# Power_Dev_revA_2.net
KiCad netlist of a schematic drawn in EAGLE
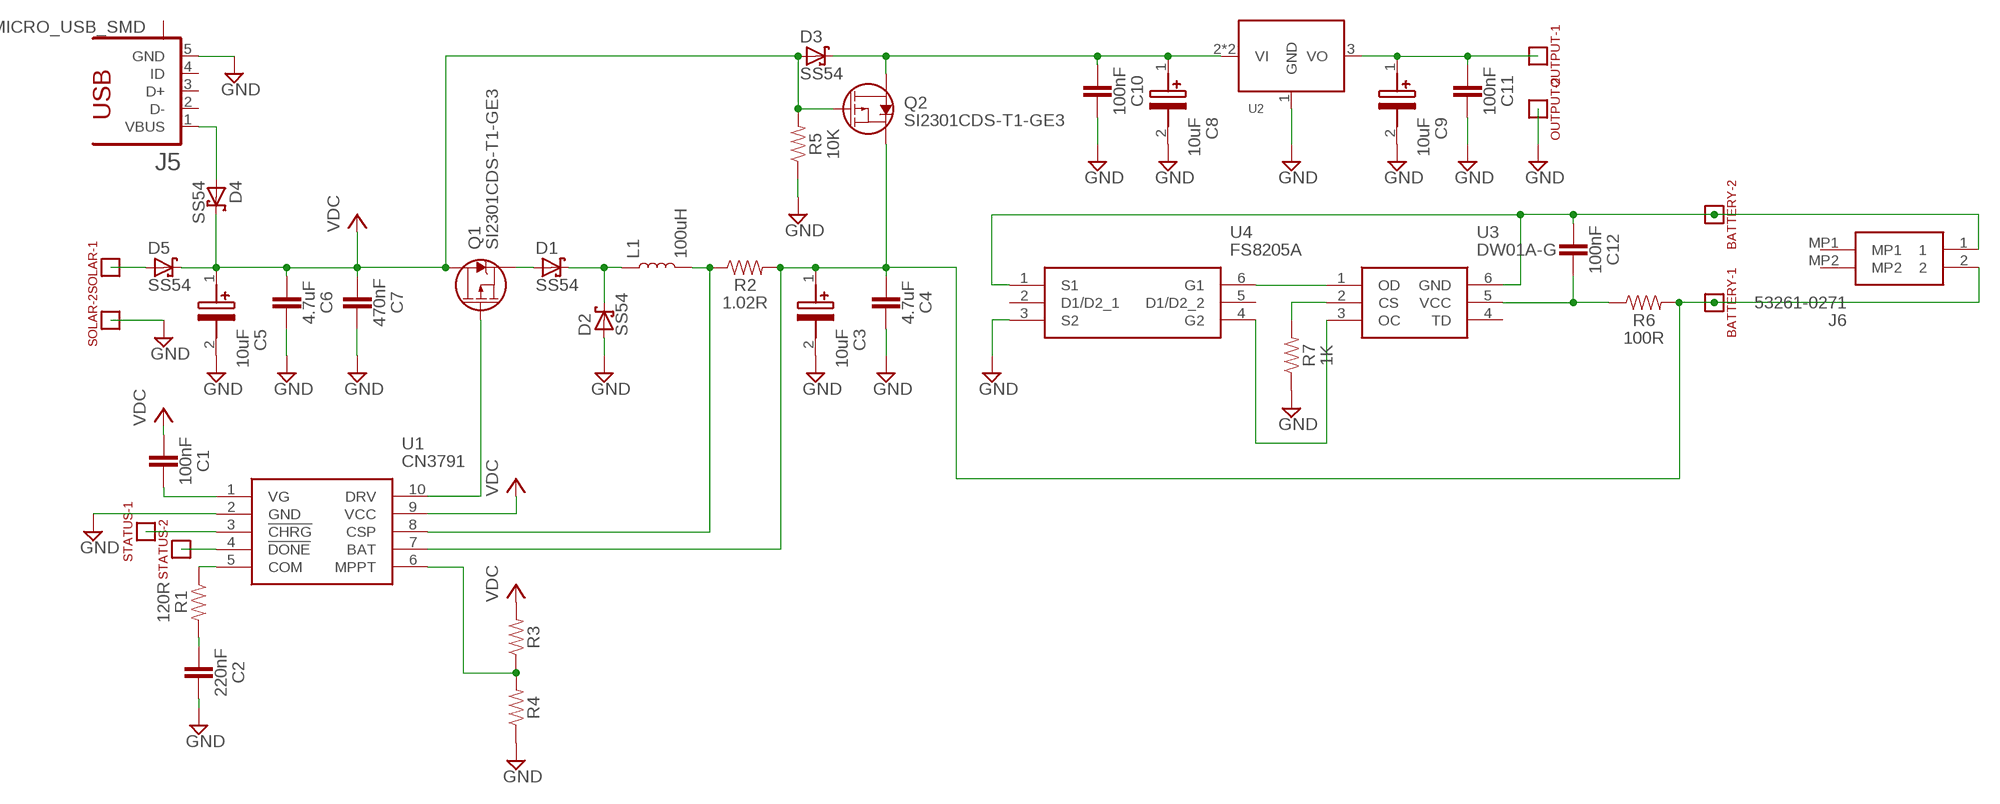
[diagram p0: schematic, sheet 1]

(export (version "E")
  (design (tool "Eeschema 10.0.6"))
  (components
    (comp (ref "BATTERY")
      (value "HEADER_2PIN")
      (footprint "eagle-import:HEADER_2PIN")
      (libsource (lib "eagle-import") (part "HEADER_2PIN"))
    )
    (comp (ref "C1")
      (value "100nF")
      (footprint "eagle-import:0402")
      (libsource (lib "eagle-import") (part "C_0402"))
    )
    (comp (ref "C2")
      (value "220nF")
      (footprint "eagle-import:0603")
      (libsource (lib "eagle-import") (part "C_0603"))
    )
    (comp (ref "C3")
      (value "10uF")
      (footprint "eagle-import:6MM_SMD_ECAP")
      (libsource (lib "eagle-import") (part "6.3MM_SMD_ECAP"))
    )
    (comp (ref "C4")
      (value "4.7uF")
      (footprint "eagle-import:1206")
      (libsource (lib "eagle-import") (part "C_1206"))
    )
    (comp (ref "C5")
      (value "10uF")
      (footprint "eagle-import:6MM_SMD_ECAP")
      (libsource (lib "eagle-import") (part "6.3MM_SMD_ECAP"))
    )
    (comp (ref "C6")
      (value "4.7uF")
      (footprint "eagle-import:1206")
      (libsource (lib "eagle-import") (part "C_1206"))
    )
    (comp (ref "C7")
      (value "470nF")
      (footprint "eagle-import:0805")
      (libsource (lib "eagle-import") (part "C_0805"))
    )
    (comp (ref "C8")
      (value "10uF")
      (footprint "eagle-import:6MM_SMD_ECAP")
      (libsource (lib "eagle-import") (part "6.3MM_SMD_ECAP"))
    )
    (comp (ref "C9")
      (value "10uF")
      (footprint "eagle-import:6MM_SMD_ECAP")
      (libsource (lib "eagle-import") (part "6.3MM_SMD_ECAP"))
    )
    (comp (ref "C10")
      (value "100nF")
      (footprint "eagle-import:0402")
      (libsource (lib "eagle-import") (part "C_0402"))
    )
    (comp (ref "C11")
      (value "100nF")
      (footprint "eagle-import:0402")
      (libsource (lib "eagle-import") (part "C_0402"))
    )
    (comp (ref "C12")
      (value "100nF")
      (footprint "eagle-import:0402")
      (libsource (lib "eagle-import") (part "C_0402"))
    )
    (comp (ref "D1")
      (value "SS54")
      (footprint "eagle-import:SMA(DO-214AC)")
      (libsource (lib "eagle-import") (part "DIODE_SCHOTTKY_SMA"))
    )
    (comp (ref "D2")
      (value "SS54")
      (footprint "eagle-import:SMA(DO-214AC)")
      (libsource (lib "eagle-import") (part "DIODE_SCHOTTKY_SMA"))
    )
    (comp (ref "D3")
      (value "SS54")
      (footprint "eagle-import:SMA(DO-214AC)")
      (libsource (lib "eagle-import") (part "DIODE_SCHOTTKY_SMA"))
    )
    (comp (ref "D4")
      (value "SS54")
      (footprint "eagle-import:SMA(DO-214AC)")
      (libsource (lib "eagle-import") (part "DIODE_SCHOTTKY_SMA"))
    )
    (comp (ref "D5")
      (value "SS54")
      (footprint "eagle-import:SMA(DO-214AC)")
      (libsource (lib "eagle-import") (part "DIODE_SCHOTTKY_SMA"))
    )
    (comp (ref "J5")
      (value "MICRO_USB_SMD")
      (footprint "eagle-import:10118192-0002LF")
      (libsource (lib "eagle-import") (part "MICRO_USB_SMD"))
    )
    (comp (ref "J6")
      (value "53261-0271")
      (footprint "eagle-import:532610271")
      (fields (field (name "MOUSER_PART_NUMBER") "538-53261-0271"))
      (libsource (lib "eagle-import") (part "53261-0271"))
    )
    (comp (ref "L1")
      (value "100uH")
      (footprint "eagle-import:L_SMD,7X7.8MM")
      (libsource (lib "eagle-import") (part "L_SMD,7X7.8MM"))
    )
    (comp (ref "OUTPUT")
      (value "HEADER_2PIN")
      (footprint "eagle-import:HEADER_2PIN")
      (libsource (lib "eagle-import") (part "HEADER_2PIN"))
    )
    (comp (ref "Q1")
      (value "SI2301CDS-T1-GE3")
      (footprint "eagle-import:SOT-23")
      (libsource (lib "eagle-import") (part "MOSFET_P_SOT23"))
    )
    (comp (ref "Q2")
      (value "SI2301CDS-T1-GE3")
      (footprint "eagle-import:SOT-23")
      (libsource (lib "eagle-import") (part "MOSFET_P_SOT23"))
    )
    (comp (ref "R1")
      (value "120R")
      (footprint "eagle-import:0805")
      (libsource (lib "eagle-import") (part "R_0805"))
    )
    (comp (ref "R2")
      (value "1.02R")
      (footprint "eagle-import:1206")
      (libsource (lib "eagle-import") (part "R_1206"))
    )
    (comp (ref "R3")
      (value "RESISTOR_TH")
      (footprint "eagle-import:RESISTOR_TH")
      (libsource (lib "eagle-import") (part "RESISTOR_TH"))
    )
    (comp (ref "R4")
      (value "RESISTOR_TH")
      (footprint "eagle-import:RESISTOR_TH")
      (libsource (lib "eagle-import") (part "RESISTOR_TH"))
    )
    (comp (ref "R5")
      (value "10K")
      (footprint "eagle-import:0402")
      (libsource (lib "eagle-import") (part "R_0402"))
    )
    (comp (ref "R6")
      (value "100R")
      (footprint "eagle-import:0402")
      (libsource (lib "eagle-import") (part "R_0402"))
    )
    (comp (ref "R7")
      (value "1K")
      (footprint "eagle-import:0402")
      (libsource (lib "eagle-import") (part "R_0402"))
    )
    (comp (ref "SOLAR")
      (value "HEADER_2PIN")
      (footprint "eagle-import:HEADER_2PIN")
      (libsource (lib "eagle-import") (part "HEADER_2PIN"))
    )
    (comp (ref "STATUS")
      (value "HEADER_2PIN")
      (footprint "eagle-import:HEADER_2PIN")
      (libsource (lib "eagle-import") (part "HEADER_2PIN"))
    )
    (comp (ref "U1")
      (value "CN3791")
      (footprint "eagle-import:SOP100P600X175-10N")
      (libsource (lib "eagle-import") (part "CN3791"))
    )
    (comp (ref "U2")
      (value "LDO_SOT89")
      (footprint "eagle-import:SOT-89-3")
      (libsource (lib "eagle-import") (part "LDO_SOT89"))
    )
    (comp (ref "U3")
      (value "DW01A-G")
      (footprint "eagle-import:SOT95P280X135-6N")
      (libsource (lib "eagle-import") (part "DW01A-G"))
    )
    (comp (ref "U4")
      (value "FS8205A")
      (footprint "eagle-import:SOT95P280X125-6N")
      (libsource (lib "eagle-import") (part "FS8205A"))
    )
  )
  (nets
    (net (code "1") (name "GND") (class "Default")
      (node (ref "C10") (pin "2") (pinfunction "2_2") (pintype "passive"))
      (node (ref "C11") (pin "2") (pinfunction "2_2") (pintype "passive"))
      (node (ref "C2") (pin "2") (pinfunction "2_2") (pintype "passive"))
      (node (ref "C3") (pin "2") (pinfunction "-_2") (pintype "bidirectional"))
      (node (ref "C4") (pin "2") (pinfunction "2_2") (pintype "passive"))
      (node (ref "C5") (pin "2") (pinfunction "-_2") (pintype "bidirectional"))
      (node (ref "C6") (pin "2") (pinfunction "2_2") (pintype "passive"))
      (node (ref "C7") (pin "2") (pinfunction "2_2") (pintype "passive"))
      (node (ref "C8") (pin "2") (pinfunction "-_2") (pintype "bidirectional"))
      (node (ref "C9") (pin "2") (pinfunction "-_2") (pintype "bidirectional"))
      (node (ref "D2") (pin "2") (pinfunction "A_2") (pintype "passive"))
      (node (ref "J5") (pin "5") (pinfunction "GND_5") (pintype "passive"))
      (node (ref "OUTPUT") (pin "P$2") (pinfunction "P$1_P$2") (pintype "bidirectional"))
      (node (ref "R4") (pin "P$1") (pinfunction "1_P$1") (pintype "passive"))
      (node (ref "R5") (pin "1") (pinfunction "1_1") (pintype "passive"))
      (node (ref "R7") (pin "1") (pinfunction "1_1") (pintype "passive"))
      (node (ref "SOLAR") (pin "P$2") (pinfunction "P$1_P$2") (pintype "bidirectional"))
      (node (ref "U1") (pin "2") (pinfunction "GND_2") (pintype "bidirectional"))
      (node (ref "U2") (pin "1") (pinfunction "GND_1") (pintype "bidirectional"))
      (node (ref "U4") (pin "3") (pinfunction "S2_3") (pintype "bidirectional"))
    )
    (net (code "2") (name "Net-(BATTERYB-P$1)") (class "Default")
      (node (ref "BATTERY") (pin "P$2") (pinfunction "P$1_P$2") (pintype "bidirectional"))
      (node (ref "C12") (pin "1") (pinfunction "1_1") (pintype "passive"))
      (node (ref "J6") (pin "1") (pinfunction "1_1") (pintype "bidirectional"))
      (node (ref "U3") (pin "6") (pinfunction "GND_6") (pintype "bidirectional"))
      (node (ref "U4") (pin "1") (pinfunction "S1_1") (pintype "bidirectional"))
    )
    (net (code "3") (name "Net-(C2-Pad1)") (class "Default")
      (node (ref "C2") (pin "1") (pinfunction "1_1") (pintype "passive"))
      (node (ref "R1") (pin "2") (pinfunction "2_2") (pintype "passive"))
    )
    (net (code "4") (name "Net-(C3-+)") (class "Default")
      (node (ref "BATTERY") (pin "P$1") (pinfunction "P$1_P$1") (pintype "bidirectional"))
      (node (ref "C3") (pin "1") (pinfunction "+_1") (pintype "bidirectional"))
      (node (ref "C4") (pin "1") (pinfunction "1_1") (pintype "passive"))
      (node (ref "J6") (pin "2") (pinfunction "2_2") (pintype "bidirectional"))
      (node (ref "Q2") (pin "3") (pinfunction "S_3") (pintype "bidirectional"))
      (node (ref "R2") (pin "2") (pinfunction "2_2") (pintype "passive"))
      (node (ref "R6") (pin "2") (pinfunction "2_2") (pintype "passive"))
      (node (ref "U1") (pin "7") (pinfunction "BAT_7") (pintype "bidirectional"))
    )
    (net (code "5") (name "Net-(C8-+)") (class "Default")
      (node (ref "C10") (pin "1") (pinfunction "1_1") (pintype "passive"))
      (node (ref "C8") (pin "1") (pinfunction "+_1") (pintype "bidirectional"))
      (node (ref "D3") (pin "1") (pinfunction "C_1") (pintype "passive"))
      (node (ref "Q2") (pin "2") (pinfunction "D_2") (pintype "bidirectional"))
      (node (ref "U2") (pin "2") (pinfunction "VI_2") (pintype "bidirectional"))
      (node (ref "U2") (pin "4") (pinfunction "VI_4") (pintype "bidirectional"))
    )
    (net (code "6") (name "Net-(C9-+)") (class "Default")
      (node (ref "C11") (pin "1") (pinfunction "1_1") (pintype "passive"))
      (node (ref "C9") (pin "1") (pinfunction "+_1") (pintype "bidirectional"))
      (node (ref "OUTPUT") (pin "P$1") (pinfunction "P$1_P$1") (pintype "bidirectional"))
      (node (ref "U2") (pin "3") (pinfunction "VO_3") (pintype "bidirectional"))
    )
    (net (code "7") (name "Net-(D1-A)") (class "Default")
      (node (ref "D1") (pin "2") (pinfunction "A_2") (pintype "passive"))
      (node (ref "Q1") (pin "3") (pinfunction "S_3") (pintype "bidirectional"))
    )
    (net (code "8") (name "Net-(D1-C)") (class "Default")
      (node (ref "D1") (pin "1") (pinfunction "C_1") (pintype "passive"))
      (node (ref "D2") (pin "1") (pinfunction "C_1") (pintype "passive"))
      (node (ref "L1") (pin "P$1") (pinfunction "1_P$1") (pintype "passive"))
    )
    (net (code "9") (name "Net-(D4-A)") (class "Default")
      (node (ref "D4") (pin "2") (pinfunction "A_2") (pintype "passive"))
      (node (ref "J5") (pin "1") (pinfunction "VBUS_1") (pintype "passive"))
    )
    (net (code "10") (name "Net-(D5-A)") (class "Default")
      (node (ref "D5") (pin "2") (pinfunction "A_2") (pintype "passive"))
      (node (ref "SOLAR") (pin "P$1") (pinfunction "P$1_P$1") (pintype "bidirectional"))
    )
    (net (code "11") (name "Net-(L1-2)") (class "Default")
      (node (ref "L1") (pin "P$2") (pinfunction "2_P$2") (pintype "passive"))
      (node (ref "R2") (pin "1") (pinfunction "1_1") (pintype "passive"))
      (node (ref "U1") (pin "8") (pinfunction "CSP_8") (pintype "bidirectional"))
    )
    (net (code "12") (name "Net-(Q1-G)") (class "Default")
      (node (ref "Q1") (pin "1") (pinfunction "G_1") (pintype "bidirectional"))
      (node (ref "U1") (pin "10") (pinfunction "DRV_10") (pintype "bidirectional"))
    )
    (net (code "13") (name "Net-(R3-1)") (class "Default")
      (node (ref "R3") (pin "P$1") (pinfunction "1_P$1") (pintype "passive"))
      (node (ref "R4") (pin "P$2") (pinfunction "2_P$2") (pintype "passive"))
      (node (ref "U1") (pin "6") (pinfunction "MPPT_6") (pintype "bidirectional"))
    )
    (net (code "14") (name "Net-(STATUSB-P$1)") (class "Default")
      (node (ref "STATUS") (pin "P$2") (pinfunction "P$1_P$2") (pintype "bidirectional"))
      (node (ref "U1") (pin "4") (pinfunction "~{DONE}_4") (pintype "bidirectional"))
    )
    (net (code "15") (name "Net-(U1-COM)") (class "Default")
      (node (ref "R1") (pin "1") (pinfunction "1_1") (pintype "passive"))
      (node (ref "U1") (pin "5") (pinfunction "COM_5") (pintype "bidirectional"))
    )
    (net (code "16") (name "Net-(U1-VG)") (class "Default")
      (node (ref "C1") (pin "2") (pinfunction "2_2") (pintype "passive"))
      (node (ref "U1") (pin "1") (pinfunction "VG_1") (pintype "bidirectional"))
    )
    (net (code "17") (name "Net-(U1-~{CHRG})") (class "Default")
      (node (ref "STATUS") (pin "P$1") (pinfunction "P$1_P$1") (pintype "bidirectional"))
      (node (ref "U1") (pin "3") (pinfunction "~{CHRG}_3") (pintype "bidirectional"))
    )
    (net (code "18") (name "Net-(U3-CS)") (class "Default")
      (node (ref "R7") (pin "2") (pinfunction "2_2") (pintype "passive"))
      (node (ref "U3") (pin "2") (pinfunction "CS_2") (pintype "bidirectional"))
    )
    (net (code "19") (name "Net-(U3-OC)") (class "Default")
      (node (ref "U3") (pin "3") (pinfunction "OC_3") (pintype "bidirectional"))
      (node (ref "U4") (pin "4") (pinfunction "G2_4") (pintype "bidirectional"))
    )
    (net (code "20") (name "Net-(U3-OD)") (class "Default")
      (node (ref "U3") (pin "1") (pinfunction "OD_1") (pintype "bidirectional"))
      (node (ref "U4") (pin "6") (pinfunction "G1_6") (pintype "bidirectional"))
    )
    (net (code "21") (name "Net-(U3-VCC)") (class "Default")
      (node (ref "C12") (pin "2") (pinfunction "2_2") (pintype "passive"))
      (node (ref "R6") (pin "1") (pinfunction "1_1") (pintype "passive"))
      (node (ref "U3") (pin "5") (pinfunction "VCC_5") (pintype "bidirectional"))
    )
    (net (code "22") (name "VDC") (class "Default")
      (node (ref "C1") (pin "1") (pinfunction "1_1") (pintype "passive"))
      (node (ref "C5") (pin "1") (pinfunction "+_1") (pintype "bidirectional"))
      (node (ref "C6") (pin "1") (pinfunction "1_1") (pintype "passive"))
      (node (ref "C7") (pin "1") (pinfunction "1_1") (pintype "passive"))
      (node (ref "D3") (pin "2") (pinfunction "A_2") (pintype "passive"))
      (node (ref "D4") (pin "1") (pinfunction "C_1") (pintype "passive"))
      (node (ref "D5") (pin "1") (pinfunction "C_1") (pintype "passive"))
      (node (ref "Q1") (pin "2") (pinfunction "D_2") (pintype "bidirectional"))
      (node (ref "Q2") (pin "1") (pinfunction "G_1") (pintype "bidirectional"))
      (node (ref "R3") (pin "P$2") (pinfunction "2_P$2") (pintype "passive"))
      (node (ref "R5") (pin "2") (pinfunction "2_2") (pintype "passive"))
      (node (ref "U1") (pin "9") (pinfunction "VCC_9") (pintype "bidirectional"))
    )
    (net (code "23") (name "unconnected-(J5-D+-Pad3)") (class "Default")
      (node (ref "J5") (pin "3") (pinfunction "D+_3") (pintype "passive"))
    )
    (net (code "24") (name "unconnected-(J5-D--Pad2)") (class "Default")
      (node (ref "J5") (pin "2") (pinfunction "D-_2") (pintype "passive"))
    )
    (net (code "25") (name "unconnected-(J5-ID-Pad4)") (class "Default")
      (node (ref "J5") (pin "4") (pinfunction "ID_4") (pintype "passive"))
    )
    (net (code "26") (name "unconnected-(J5-PadS1)") (class "Default")
      (node (ref "J5") (pin "S1") (pinfunction "S1_S1") (pintype "passive"))
    )
    (net (code "27") (name "unconnected-(J6-PadMP1)") (class "Default")
      (node (ref "J6") (pin "MP1") (pinfunction "MP1_MP1") (pintype "bidirectional"))
    )
    (net (code "28") (name "unconnected-(J6-PadMP2)") (class "Default")
      (node (ref "J6") (pin "MP2") (pinfunction "MP2_MP2") (pintype "bidirectional"))
    )
    (net (code "29") (name "unconnected-(U3-TD-Pad4)") (class "Default")
      (node (ref "U3") (pin "4") (pinfunction "TD_4") (pintype "bidirectional"))
    )
    (net (code "30") (name "unconnected-(U4-D1{slash}D2_1-Pad2)") (class "Default")
      (node (ref "U4") (pin "2") (pinfunction "D1/D2_1_2") (pintype "bidirectional"))
    )
    (net (code "31") (name "unconnected-(U4-D1{slash}D2_2-Pad5)") (class "Default")
      (node (ref "U4") (pin "5") (pinfunction "D1/D2_2_5") (pintype "bidirectional"))
    )
  )
)
